# stm32f4.net
KiCad netlist of a schematic drawn in Altium Designer
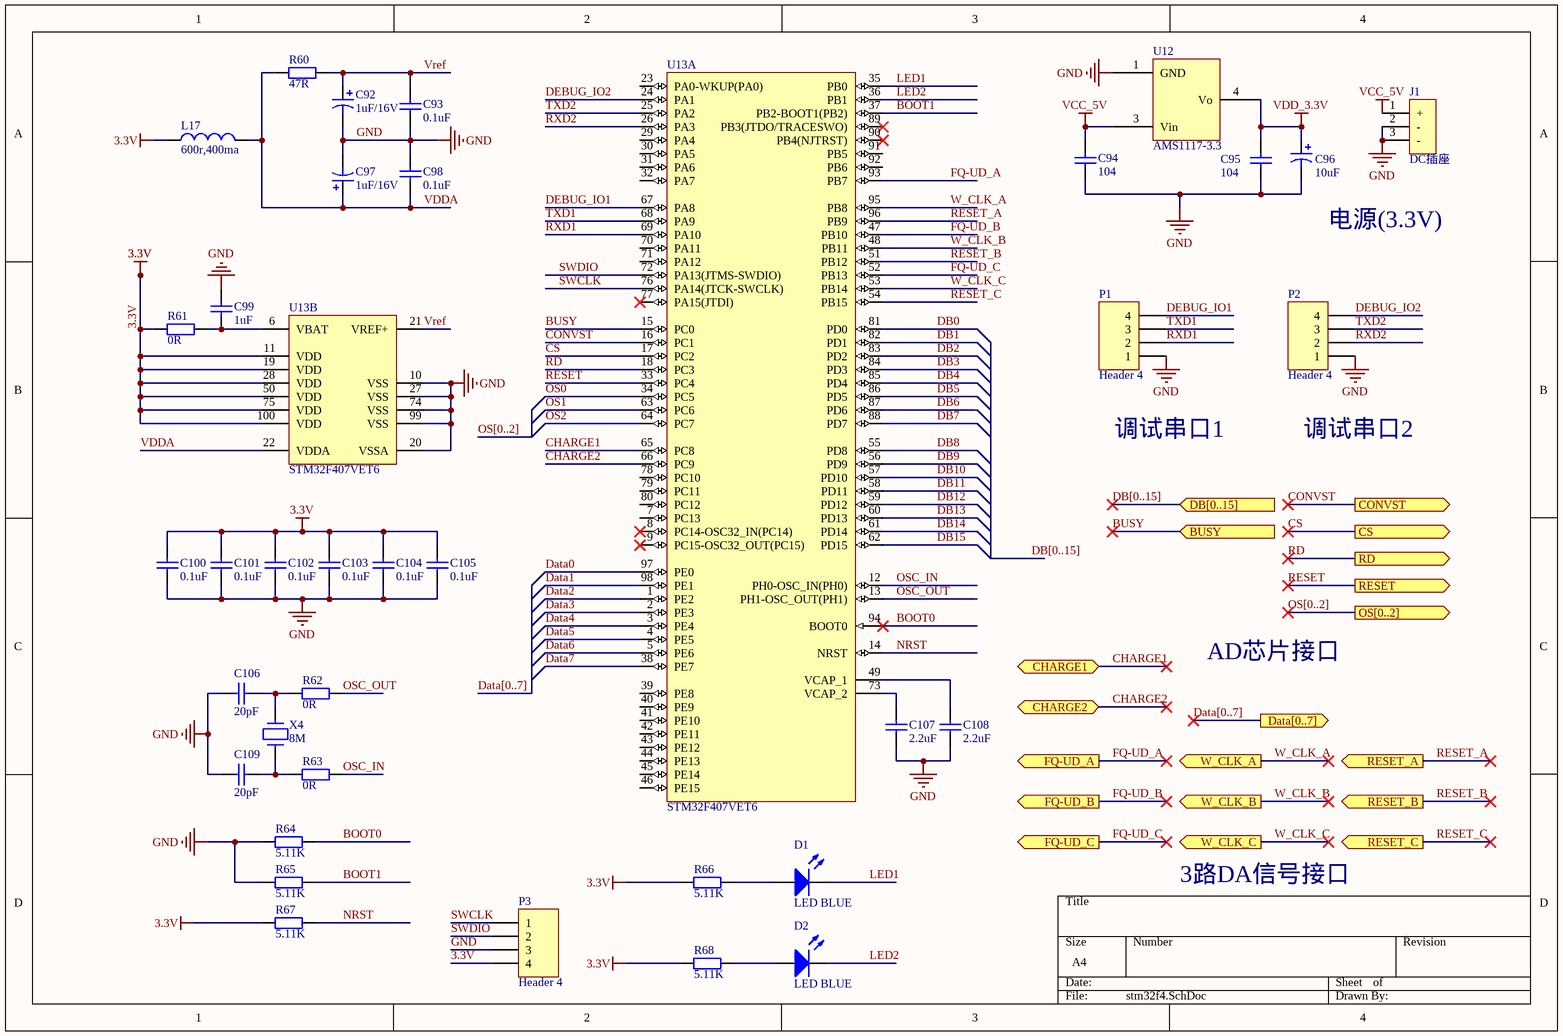
[diagram p0: stm32f4.SchDoc]

(export (version "E")
  (design (tool "Eeschema 10.0.6"))
  (components
    (comp (ref "C92") (value "1uF/16V") (footprint "1206") (libsource (lib "MyLibrary") (part "Cap_Pol")))
    (comp (ref "C93") (value "0.1uF") (footprint "0805C") (libsource (lib "MyLibrary") (part "Cap")))
    (comp (ref "C94")
      (value "104")
      (footprint "0805")
      (fields
        (field (name "Comment") "Cap")
        (field (name "原理图绘制者") "刘永钦")
        (field (name "原理图提供者") "刘永钦")
        (field (name "原理图审核人1") "徐鹏飞")
        (field (name "封装0805绘制者") "刘永钦")
        (field (name "封装0805提供者") "刘永钦")
        (field (name "封装0805审核人1") "徐鹏飞")
        (field (name "原理图审核人2") "朱觉文")
        (field (name "封装0805审核人2") "朱觉文")
        (field (name "封装0603绘制者") "刘永钦")
        (field (name "封装0603提供者") "刘永钦")
        (field (name "封装0603审核人1") "朱觉文")
        (field (name "封装0603审核人2") "徐鹏飞")
      )
      (libsource (lib "自动化研究所集成库20170318") (part "Cap"))
    )
    (comp (ref "C95")
      (value "104")
      (footprint "0805")
      (fields
        (field (name "Comment") "Cap")
        (field (name "原理图绘制者") "刘永钦")
        (field (name "原理图提供者") "刘永钦")
        (field (name "原理图审核人1") "徐鹏飞")
        (field (name "封装0805绘制者") "刘永钦")
        (field (name "封装0805提供者") "刘永钦")
        (field (name "封装0805审核人1") "徐鹏飞")
        (field (name "原理图审核人2") "朱觉文")
        (field (name "封装0805审核人2") "朱觉文")
        (field (name "封装0603绘制者") "刘永钦")
        (field (name "封装0603提供者") "刘永钦")
        (field (name "封装0603审核人1") "朱觉文")
        (field (name "封装0603审核人2") "徐鹏飞")
      )
      (libsource (lib "自动化研究所集成库20170318") (part "Cap"))
    )
    (comp (ref "C96")
      (value "10uF")
      (footprint "Cap 3528B")
      (fields
        (field (name "Comment") "Cap Poll")
        (field (name "原理图绘制者") "刘永钦")
        (field (name "原理图提供者") "刘永钦")
        (field (name "原理图审核人1") "徐鹏飞")
        (field (name "封装CAP 钽 7343 E绘制者") "刘永钦")
        (field (name "封装CAP 钽 7343 E提供者") "刘永钦")
        (field (name "封装CAP 钽 7343 E审核人1") "徐鹏飞")
        (field (name "封装CAP贴片铝电解质470UF 16V绘制者") "李泽")
        (field (name "封装CAP贴片铝电解质470UF 16V提供者") "刘永钦")
        (field (name "封装CAP贴片铝电解质470UF 16V审核人1") "徐鹏飞")
        (field (name "封装CAP 3528B绘制者") "陈汉诚")
        (field (name "封装CAP 3528B提供者") "刘永钦")
        (field (name "封装CAP 3528B审核人1") "徐鹏飞")
        (field (name "封装CAP直插 10UF 50V提供者") "刘永钦")
        (field (name "封装CAP直插 10UF 50V审核人1") "徐鹏飞")
        (field (name "封装CAP 3528B审核人2") "朱觉文")
        (field (name "封装CAP直插 10UF 50V审核人2") "朱觉文")
        (field (name "封装CAP贴片铝电解质470UF 16V审核人2") "朱觉文")
        (field (name "封装CAP 钽 7343 E审核人2") "朱觉文")
        (field (name "原理图审核人2") "朱觉文")
      )
      (libsource (lib "自动化研究所集成库20170318") (part "Cap Poll"))
    )
    (comp (ref "C97") (value "1uF/16V") (footprint "1206") (libsource (lib "MyLibrary") (part "Cap_Pol")))
    (comp (ref "C98") (value "0.1uF") (footprint "0805C") (libsource (lib "MyLibrary") (part "Cap")))
    (comp (ref "C99") (value "1uF") (footprint "0805C") (libsource (lib "MyLibrary") (part "Cap")))
    (comp (ref "C100") (value "0.1uF") (footprint "0805C") (libsource (lib "MyLibrary") (part "Cap")))
    (comp (ref "C101") (value "0.1uF") (footprint "0805C") (libsource (lib "MyLibrary") (part "Cap")))
    (comp (ref "C102") (value "0.1uF") (footprint "0805C") (libsource (lib "MyLibrary") (part "Cap")))
    (comp (ref "C103") (value "0.1uF") (footprint "0805C") (libsource (lib "MyLibrary") (part "Cap")))
    (comp (ref "C104") (value "0.1uF") (footprint "0805C") (libsource (lib "MyLibrary") (part "Cap")))
    (comp (ref "C105") (value "0.1uF") (footprint "0805C") (libsource (lib "MyLibrary") (part "Cap")))
    (comp (ref "C106") (value "20pF") (footprint "0805C") (libsource (lib "MyLibrary") (part "Cap")))
    (comp (ref "C107") (value "2.2uF") (footprint "0805C") (libsource (lib "MyLibrary") (part "Cap")))
    (comp (ref "C108") (value "2.2uF") (footprint "0805C") (libsource (lib "MyLibrary") (part "Cap")))
    (comp (ref "C109") (value "20pF") (footprint "0805C") (libsource (lib "MyLibrary") (part "Cap")))
    (comp (ref "D1") (value "LED BLUE") (footprint "LED_3mm") (libsource (lib "MyLibrary") (part "LED")))
    (comp (ref "D2") (value "LED BLUE") (footprint "LED_3mm") (libsource (lib "MyLibrary") (part "LED")))
    (comp (ref "J1")
      (value "DC插座")
      (footprint "DC插座 5.5mm*2.1mm")
      (fields
        (field (name "原理图审核人2") "朱觉文")
        (field (name "原理图提供者") "刘永钦")
        (field (name "原理图审核人1") "徐鹏飞")
        (field (name "原理图绘制者") "刘永钦")
        (field (name "封装DC插座 5.5MM*2.1MM绘制者") "刘永钦")
        (field (name "封装DC插座 5.5MM*2.1MM提供者") "刘永钦")
        (field (name "封装DC插座 5.5MM*2.1MM审核人1") "徐鹏飞")
        (field (name "封装DC插座 5.5MM*2.1MM审核人2") "朱觉文")
      )
      (libsource (lib "自动化研究所集成库20170318") (part "DC插座"))
    )
    (comp (ref "L17")
      (value "600r,400ma")
      (footprint "0805L")
      (libsource (lib "MyLibrary") (part "Inductor"))
    )
    (comp (ref "P1")
      (value "Header 4")
      (footprint "HDR1X4")
      (description "Header, 4-Pin")
      (fields (field (name "PUBLISHER") "Altium Limited"))
      (libsource (lib "Miscellaneous Connectors") (part "Header 4"))
    )
    (comp (ref "P2")
      (value "Header 4")
      (footprint "HDR1X4")
      (description "Header, 4-Pin")
      (fields (field (name "PUBLISHER") "Altium Limited"))
      (libsource (lib "Miscellaneous Connectors") (part "Header 4"))
    )
    (comp (ref "P3")
      (value "Header 4")
      (footprint "HDR1X4")
      (description "Header, 4-Pin")
      (fields (field (name "PUBLISHER") "Altium Limited"))
      (libsource (lib "") (part "Header 4_1"))
    )
    (comp (ref "R60") (value "47R") (footprint "0805R") (libsource (lib "MyLibrary") (part "Res")))
    (comp (ref "R61") (value "0R") (footprint "0805R") (libsource (lib "MyLibrary") (part "Res")))
    (comp (ref "R62") (value "0R") (footprint "0805R") (libsource (lib "MyLibrary") (part "Res")))
    (comp (ref "R63") (value "0R") (footprint "0805R") (libsource (lib "MyLibrary") (part "Res")))
    (comp (ref "R64") (value "5.11K") (footprint "0805R") (libsource (lib "") (part "Res_1")))
    (comp (ref "R65") (value "5.11K") (footprint "0805R") (libsource (lib "") (part "Res_1")))
    (comp (ref "R66") (value "5.11K") (footprint "0805R") (libsource (lib "") (part "Res_1")))
    (comp (ref "R67") (value "5.11K") (footprint "0805R") (libsource (lib "") (part "Res_1")))
    (comp (ref "R68") (value "5.11K") (footprint "0805R") (libsource (lib "") (part "Res_1")))
    (comp (ref "U12")
      (value "AMS1117-3.3")
      (footprint "TO-252-2L")
      (libsource (lib "Spartan") (part "AMS1117"))
    )
    (comp (ref "U13")
      (value "STM32F407VET6")
      (footprint "pulse_power1:LQFP100")
      (libsource (lib "altium-import") (part "root_0_MC-ARM-STM32F40X_41X-SQ100_"))
    )
    (comp (ref "X4") (value "8M") (footprint "49SMD") (libsource (lib "MyLibrary") (part "Crystal")))
  )
  (nets
    (net (code "1") (name "/BOOT0") (class "Default")
      (node (ref "R64") (pin "1") (pinfunction "1_1") (pintype "passive"))
      (node (ref "U13") (pin "94") (pinfunction "BOOT0_94") (pintype "input"))
    )
    (net (code "2") (name "/BOOT1") (class "Default")
      (node (ref "R65") (pin "1") (pinfunction "1_1") (pintype "passive"))
      (node (ref "U13") (pin "37") (pinfunction "PB2-BOOT1(PB2)_37") (pintype "bidirectional"))
    )
    (net (code "3") (name "/BUSY") (class "Default")
      (node (ref "U13") (pin "15") (pinfunction "PC0_15") (pintype "bidirectional"))
    )
    (net (code "4") (name "/CHARGE1") (class "Default")
      (node (ref "U13") (pin "65") (pinfunction "PC8_65") (pintype "bidirectional"))
    )
    (net (code "5") (name "/CHARGE2") (class "Default")
      (node (ref "U13") (pin "66") (pinfunction "PC9_66") (pintype "bidirectional"))
    )
    (net (code "6") (name "/CONVST") (class "Default")
      (node (ref "U13") (pin "16") (pinfunction "PC1_16") (pintype "bidirectional"))
    )
    (net (code "7") (name "/CS") (class "Default")
      (node (ref "U13") (pin "17") (pinfunction "PC2_17") (pintype "bidirectional"))
    )
    (net (code "8") (name "/DB0") (class "Default")
      (node (ref "U13") (pin "81") (pinfunction "PD0_81") (pintype "bidirectional"))
    )
    (net (code "9") (name "/DB1") (class "Default")
      (node (ref "U13") (pin "82") (pinfunction "PD1_82") (pintype "bidirectional"))
    )
    (net (code "10") (name "/DB2") (class "Default")
      (node (ref "U13") (pin "83") (pinfunction "PD2_83") (pintype "bidirectional"))
    )
    (net (code "11") (name "/DB3") (class "Default")
      (node (ref "U13") (pin "84") (pinfunction "PD3_84") (pintype "bidirectional"))
    )
    (net (code "12") (name "/DB4") (class "Default")
      (node (ref "U13") (pin "85") (pinfunction "PD4_85") (pintype "bidirectional"))
    )
    (net (code "13") (name "/DB5") (class "Default")
      (node (ref "U13") (pin "86") (pinfunction "PD5_86") (pintype "bidirectional"))
    )
    (net (code "14") (name "/DB6") (class "Default")
      (node (ref "U13") (pin "87") (pinfunction "PD6_87") (pintype "bidirectional"))
    )
    (net (code "15") (name "/DB7") (class "Default")
      (node (ref "U13") (pin "88") (pinfunction "PD7_88") (pintype "bidirectional"))
    )
    (net (code "16") (name "/DB8") (class "Default")
      (node (ref "U13") (pin "55") (pinfunction "PD8_55") (pintype "bidirectional"))
    )
    (net (code "17") (name "/DB9") (class "Default")
      (node (ref "U13") (pin "56") (pinfunction "PD9_56") (pintype "bidirectional"))
    )
    (net (code "18") (name "/DB10") (class "Default")
      (node (ref "U13") (pin "57") (pinfunction "PD10_57") (pintype "bidirectional"))
    )
    (net (code "19") (name "/DB11") (class "Default")
      (node (ref "U13") (pin "58") (pinfunction "PD11_58") (pintype "bidirectional"))
    )
    (net (code "20") (name "/DB12") (class "Default")
      (node (ref "U13") (pin "59") (pinfunction "PD12_59") (pintype "bidirectional"))
    )
    (net (code "21") (name "/DB13") (class "Default")
      (node (ref "U13") (pin "60") (pinfunction "PD13_60") (pintype "bidirectional"))
    )
    (net (code "22") (name "/DB14") (class "Default")
      (node (ref "U13") (pin "61") (pinfunction "PD14_61") (pintype "bidirectional"))
    )
    (net (code "23") (name "/DB15") (class "Default")
      (node (ref "U13") (pin "62") (pinfunction "PD15_62") (pintype "bidirectional"))
    )
    (net (code "25") (name "/DEBUG_IO1") (class "Default")
      (node (ref "P1") (pin "4") (pinfunction "4_4") (pintype "passive"))
      (node (ref "U13") (pin "67") (pinfunction "PA8_67") (pintype "bidirectional"))
    )
    (net (code "26") (name "/DEBUG_IO2") (class "Default")
      (node (ref "P2") (pin "4") (pinfunction "4_4") (pintype "passive"))
      (node (ref "U13") (pin "24") (pinfunction "PA1_24") (pintype "bidirectional"))
    )
    (net (code "27") (name "/Data0") (class "Default")
      (node (ref "U13") (pin "97") (pinfunction "PE0_97") (pintype "bidirectional"))
    )
    (net (code "28") (name "/Data1") (class "Default")
      (node (ref "U13") (pin "98") (pinfunction "PE1_98") (pintype "bidirectional"))
    )
    (net (code "29") (name "/Data2") (class "Default")
      (node (ref "U13") (pin "1") (pinfunction "PE2_1") (pintype "bidirectional"))
    )
    (net (code "30") (name "/Data3") (class "Default")
      (node (ref "U13") (pin "2") (pinfunction "PE3_2") (pintype "bidirectional"))
    )
    (net (code "31") (name "/Data4") (class "Default")
      (node (ref "U13") (pin "3") (pinfunction "PE4_3") (pintype "bidirectional"))
    )
    (net (code "32") (name "/Data5") (class "Default")
      (node (ref "U13") (pin "4") (pinfunction "PE5_4") (pintype "bidirectional"))
    )
    (net (code "33") (name "/Data6") (class "Default")
      (node (ref "U13") (pin "5") (pinfunction "PE6_5") (pintype "bidirectional"))
    )
    (net (code "34") (name "/Data7") (class "Default")
      (node (ref "U13") (pin "38") (pinfunction "PE7_38") (pintype "bidirectional"))
    )
    (net (code "36") (name "/FQ-UD_A") (class "Default")
      (node (ref "U13") (pin "93") (pinfunction "PB7_93") (pintype "bidirectional"))
    )
    (net (code "37") (name "/FQ-UD_B") (class "Default")
      (node (ref "U13") (pin "47") (pinfunction "PB10_47") (pintype "bidirectional"))
    )
    (net (code "38") (name "/FQ-UD_C") (class "Default")
      (node (ref "U13") (pin "52") (pinfunction "PB13_52") (pintype "bidirectional"))
    )
    (net (code "39") (name "/LED1") (class "Default")
      (node (ref "D1") (pin "2") (pinfunction "K_2") (pintype "passive"))
      (node (ref "U13") (pin "35") (pinfunction "PB0_35") (pintype "bidirectional"))
    )
    (net (code "40") (name "/LED2") (class "Default")
      (node (ref "D2") (pin "2") (pinfunction "K_2") (pintype "passive"))
      (node (ref "U13") (pin "36") (pinfunction "PB1_36") (pintype "bidirectional"))
    )
    (net (code "41") (name "/NRST") (class "Default")
      (node (ref "R67") (pin "1") (pinfunction "1_1") (pintype "passive"))
      (node (ref "U13") (pin "14") (pinfunction "NRST_14") (pintype "bidirectional"))
    )
    (net (code "42") (name "/OS0") (class "Default")
      (node (ref "U13") (pin "34") (pinfunction "PC5_34") (pintype "bidirectional"))
    )
    (net (code "43") (name "/OS1") (class "Default")
      (node (ref "U13") (pin "63") (pinfunction "PC6_63") (pintype "bidirectional"))
    )
    (net (code "44") (name "/OS2") (class "Default")
      (node (ref "U13") (pin "64") (pinfunction "PC7_64") (pintype "bidirectional"))
    )
    (net (code "45") (name "/OSC_IN") (class "Default")
      (node (ref "R63") (pin "2") (pinfunction "2_2") (pintype "passive"))
      (node (ref "U13") (pin "12") (pinfunction "PH0-OSC_IN(PH0)_12") (pintype "bidirectional"))
    )
    (net (code "46") (name "/OSC_OUT") (class "Default")
      (node (ref "R62") (pin "2") (pinfunction "2_2") (pintype "passive"))
      (node (ref "U13") (pin "13") (pinfunction "PH1-OSC_OUT(PH1)_13") (pintype "bidirectional"))
    )
    (net (code "48") (name "/RD") (class "Default")
      (node (ref "U13") (pin "18") (pinfunction "PC3_18") (pintype "bidirectional"))
    )
    (net (code "49") (name "/RESET") (class "Default")
      (node (ref "U13") (pin "33") (pinfunction "PC4_33") (pintype "bidirectional"))
    )
    (net (code "50") (name "/RESET_A") (class "Default")
      (node (ref "U13") (pin "96") (pinfunction "PB9_96") (pintype "bidirectional"))
    )
    (net (code "51") (name "/RESET_B") (class "Default")
      (node (ref "U13") (pin "51") (pinfunction "PB12_51") (pintype "bidirectional"))
    )
    (net (code "52") (name "/RESET_C") (class "Default")
      (node (ref "U13") (pin "54") (pinfunction "PB15_54") (pintype "bidirectional"))
    )
    (net (code "53") (name "/RXD1") (class "Default")
      (node (ref "P1") (pin "2") (pinfunction "2_2") (pintype "passive"))
      (node (ref "U13") (pin "69") (pinfunction "PA10_69") (pintype "bidirectional"))
    )
    (net (code "54") (name "/RXD2") (class "Default")
      (node (ref "P2") (pin "2") (pinfunction "2_2") (pintype "passive"))
      (node (ref "U13") (pin "26") (pinfunction "PA3_26") (pintype "bidirectional"))
    )
    (net (code "55") (name "/SWCLK") (class "Default")
      (node (ref "P3") (pin "1") (pinfunction "1_1") (pintype "passive"))
      (node (ref "U13") (pin "76") (pinfunction "PA14(JTCK-SWCLK)_76") (pintype "bidirectional"))
    )
    (net (code "56") (name "/SWDIO") (class "Default")
      (node (ref "P3") (pin "2") (pinfunction "2_2") (pintype "passive"))
      (node (ref "U13") (pin "72") (pinfunction "PA13(JTMS-SWDIO)_72") (pintype "bidirectional"))
    )
    (net (code "57") (name "/TXD1") (class "Default")
      (node (ref "P1") (pin "3") (pinfunction "3_3") (pintype "passive"))
      (node (ref "U13") (pin "68") (pinfunction "PA9_68") (pintype "bidirectional"))
    )
    (net (code "58") (name "/TXD2") (class "Default")
      (node (ref "P2") (pin "3") (pinfunction "3_3") (pintype "passive"))
      (node (ref "U13") (pin "25") (pinfunction "PA2_25") (pintype "bidirectional"))
    )
    (net (code "59") (name "/VDDA") (class "Default")
      (node (ref "C97") (pin "1") (pinfunction "1_1") (pintype "passive"))
      (node (ref "C98") (pin "1") (pinfunction "1_1") (pintype "passive"))
      (node (ref "L17") (pin "2") (pinfunction "2_2") (pintype "passive"))
      (node (ref "R60") (pin "1") (pinfunction "1_1") (pintype "passive"))
      (node (ref "U13") (pin "22") (pinfunction "VDDA_22") (pintype "power_in"))
    )
    (net (code "60") (name "/Vref") (class "Default")
      (node (ref "C92") (pin "1") (pinfunction "1_1") (pintype "passive"))
      (node (ref "C93") (pin "2") (pinfunction "2_2") (pintype "passive"))
      (node (ref "R60") (pin "2") (pinfunction "2_2") (pintype "passive"))
      (node (ref "U13") (pin "21") (pinfunction "VREF+_21") (pintype "power_in"))
    )
    (net (code "61") (name "/W_CLK_A") (class "Default")
      (node (ref "U13") (pin "95") (pinfunction "PB8_95") (pintype "bidirectional"))
    )
    (net (code "62") (name "/W_CLK_B") (class "Default")
      (node (ref "U13") (pin "48") (pinfunction "PB11_48") (pintype "bidirectional"))
    )
    (net (code "63") (name "/W_CLK_C") (class "Default")
      (node (ref "U13") (pin "53") (pinfunction "PB14_53") (pintype "bidirectional"))
    )
    (net (code "64") (name "3.3V") (class "Default")
      (node (ref "C100") (pin "2") (pinfunction "2_2") (pintype "passive"))
      (node (ref "C101") (pin "2") (pinfunction "2_2") (pintype "passive"))
      (node (ref "C102") (pin "2") (pinfunction "2_2") (pintype "passive"))
      (node (ref "C103") (pin "2") (pinfunction "2_2") (pintype "passive"))
      (node (ref "C104") (pin "2") (pinfunction "2_2") (pintype "passive"))
      (node (ref "C105") (pin "2") (pinfunction "2_2") (pintype "passive"))
      (node (ref "L17") (pin "1") (pinfunction "1_1") (pintype "passive"))
      (node (ref "P3") (pin "4") (pinfunction "4_4") (pintype "passive"))
      (node (ref "R61") (pin "1") (pinfunction "1_1") (pintype "passive"))
      (node (ref "R66") (pin "2") (pinfunction "2_2") (pintype "passive"))
      (node (ref "R67") (pin "2") (pinfunction "2_2") (pintype "passive"))
      (node (ref "R68") (pin "2") (pinfunction "2_2") (pintype "passive"))
      (node (ref "U13") (pin "100") (pinfunction "VDD_100") (pintype "power_in"))
      (node (ref "U13") (pin "11") (pinfunction "VDD_11") (pintype "power_in"))
      (node (ref "U13") (pin "19") (pinfunction "VDD_19") (pintype "power_in"))
      (node (ref "U13") (pin "28") (pinfunction "VDD_28") (pintype "power_in"))
      (node (ref "U13") (pin "50") (pinfunction "VDD_50") (pintype "power_in"))
      (node (ref "U13") (pin "75") (pinfunction "VDD_75") (pintype "power_in"))
    )
    (net (code "65") (name "GND") (class "Default")
      (node (ref "C100") (pin "1") (pinfunction "1_1") (pintype "passive"))
      (node (ref "C101") (pin "1") (pinfunction "1_1") (pintype "passive"))
      (node (ref "C102") (pin "1") (pinfunction "1_1") (pintype "passive"))
      (node (ref "C103") (pin "1") (pinfunction "1_1") (pintype "passive"))
      (node (ref "C104") (pin "1") (pinfunction "1_1") (pintype "passive"))
      (node (ref "C105") (pin "1") (pinfunction "1_1") (pintype "passive"))
      (node (ref "C106") (pin "1") (pinfunction "1_1") (pintype "passive"))
      (node (ref "C107") (pin "1") (pinfunction "1_1") (pintype "passive"))
      (node (ref "C108") (pin "1") (pinfunction "1_1") (pintype "passive"))
      (node (ref "C109") (pin "1") (pinfunction "1_1") (pintype "passive"))
      (node (ref "C92") (pin "2") (pinfunction "2_2") (pintype "passive"))
      (node (ref "C93") (pin "1") (pinfunction "1_1") (pintype "passive"))
      (node (ref "C94") (pin "1") (pinfunction "1_1") (pintype "passive"))
      (node (ref "C95") (pin "1") (pinfunction "1_1") (pintype "passive"))
      (node (ref "C96") (pin "2") (pinfunction "2_2") (pintype "passive"))
      (node (ref "C97") (pin "2") (pinfunction "2_2") (pintype "passive"))
      (node (ref "C98") (pin "2") (pinfunction "2_2") (pintype "passive"))
      (node (ref "C99") (pin "2") (pinfunction "2_2") (pintype "passive"))
      (node (ref "J1") (pin "2") (pinfunction "-_2") (pintype "power_in"))
      (node (ref "J1") (pin "3") (pinfunction "-_3") (pintype "power_in"))
      (node (ref "P1") (pin "1") (pinfunction "1_1") (pintype "passive"))
      (node (ref "P2") (pin "1") (pinfunction "1_1") (pintype "passive"))
      (node (ref "P3") (pin "3") (pinfunction "3_3") (pintype "passive"))
      (node (ref "R64") (pin "2") (pinfunction "2_2") (pintype "passive"))
      (node (ref "R65") (pin "2") (pinfunction "2_2") (pintype "passive"))
      (node (ref "U12") (pin "1") (pinfunction "GND_1") (pintype "passive"))
      (node (ref "U13") (pin "10") (pinfunction "VSS_10") (pintype "power_in"))
      (node (ref "U13") (pin "20") (pinfunction "VSSA_20") (pintype "power_in"))
      (node (ref "U13") (pin "27") (pinfunction "VSS_27") (pintype "power_in"))
      (node (ref "U13") (pin "74") (pinfunction "VSS_74") (pintype "power_in"))
      (node (ref "U13") (pin "99") (pinfunction "VSS_99") (pintype "power_in"))
    )
    (net (code "66") (name "Net-(C106-Pad2)") (class "Default")
      (node (ref "C106") (pin "2") (pinfunction "2_2") (pintype "passive"))
      (node (ref "R62") (pin "1") (pinfunction "1_1") (pintype "passive"))
      (node (ref "X4") (pin "1") (pinfunction "1_1") (pintype "passive"))
    )
    (net (code "67") (name "Net-(C109-Pad2)") (class "Default")
      (node (ref "C109") (pin "2") (pinfunction "2_2") (pintype "passive"))
      (node (ref "R63") (pin "1") (pinfunction "1_1") (pintype "passive"))
      (node (ref "X4") (pin "2") (pinfunction "2_2") (pintype "passive"))
    )
    (net (code "68") (name "Net-(D1-A)") (class "Default")
      (node (ref "D1") (pin "1") (pinfunction "A_1") (pintype "passive"))
      (node (ref "R66") (pin "1") (pinfunction "1_1") (pintype "passive"))
    )
    (net (code "69") (name "Net-(D2-A)") (class "Default")
      (node (ref "D2") (pin "1") (pinfunction "A_1") (pintype "passive"))
      (node (ref "R68") (pin "1") (pinfunction "1_1") (pintype "passive"))
    )
    (net (code "70") (name "Net-(U13A-VCAP_1)") (class "Default")
      (node (ref "C108") (pin "2") (pinfunction "2_2") (pintype "passive"))
      (node (ref "U13") (pin "49") (pinfunction "VCAP_1_49") (pintype "power_in"))
    )
    (net (code "71") (name "Net-(U13A-VCAP_2)") (class "Default")
      (node (ref "C107") (pin "2") (pinfunction "2_2") (pintype "passive"))
      (node (ref "U13") (pin "73") (pinfunction "VCAP_2_73") (pintype "power_in"))
    )
    (net (code "72") (name "Net-(U13B-VBAT)") (class "Default")
      (node (ref "C99") (pin "1") (pinfunction "1_1") (pintype "passive"))
      (node (ref "R61") (pin "2") (pinfunction "2_2") (pintype "passive"))
      (node (ref "U13") (pin "6") (pinfunction "VBAT_6") (pintype "power_in"))
    )
    (net (code "73") (name "VCC_5V") (class "Default")
      (node (ref "C94") (pin "2") (pinfunction "2_2") (pintype "passive"))
      (node (ref "J1") (pin "1") (pinfunction "+_1") (pintype "power_in"))
      (node (ref "U12") (pin "3") (pinfunction "Vin_3") (pintype "passive"))
    )
    (net (code "74") (name "VDD_3.3V") (class "Default")
      (node (ref "C95") (pin "2") (pinfunction "2_2") (pintype "passive"))
      (node (ref "C96") (pin "1") (pinfunction "1_1") (pintype "passive"))
      (node (ref "U12") (pin "4") (pinfunction "Vo_4") (pintype "passive"))
    )
    (net (code "75") (name "unconnected-(U13A-PA0-WKUP(PA0)-Pad23)") (class "Default")
      (node (ref "U13") (pin "23") (pinfunction "PA0-WKUP(PA0)_23") (pintype "bidirectional"))
    )
    (net (code "76") (name "unconnected-(U13A-PA4-Pad29)") (class "Default")
      (node (ref "U13") (pin "29") (pinfunction "PA4_29") (pintype "bidirectional"))
    )
    (net (code "77") (name "unconnected-(U13A-PA5-Pad30)") (class "Default")
      (node (ref "U13") (pin "30") (pinfunction "PA5_30") (pintype "bidirectional"))
    )
    (net (code "78") (name "unconnected-(U13A-PA6-Pad31)") (class "Default")
      (node (ref "U13") (pin "31") (pinfunction "PA6_31") (pintype "bidirectional"))
    )
    (net (code "79") (name "unconnected-(U13A-PA7-Pad32)") (class "Default")
      (node (ref "U13") (pin "32") (pinfunction "PA7_32") (pintype "bidirectional"))
    )
    (net (code "80") (name "unconnected-(U13A-PA11-Pad70)") (class "Default")
      (node (ref "U13") (pin "70") (pinfunction "PA11_70") (pintype "bidirectional"))
    )
    (net (code "81") (name "unconnected-(U13A-PA12-Pad71)") (class "Default")
      (node (ref "U13") (pin "71") (pinfunction "PA12_71") (pintype "bidirectional"))
    )
    (net (code "82") (name "unconnected-(U13A-PA15(JTDI)-Pad77)") (class "Default")
      (node (ref "U13") (pin "77") (pinfunction "PA15(JTDI)_77") (pintype "bidirectional+no_connect"))
    )
    (net (code "83") (name "unconnected-(U13A-PB3(JTDO{slash}TRACESWO)-Pad89)") (class "Default")
      (node (ref "U13") (pin "89") (pinfunction "PB3(JTDO/TRACESWO)_89") (pintype "bidirectional+no_connect"))
    )
    (net (code "84") (name "unconnected-(U13A-PB4(NJTRST)-Pad90)") (class "Default")
      (node (ref "U13") (pin "90") (pinfunction "PB4(NJTRST)_90") (pintype "bidirectional+no_connect"))
    )
    (net (code "85") (name "unconnected-(U13A-PB5-Pad91)") (class "Default")
      (node (ref "U13") (pin "91") (pinfunction "PB5_91") (pintype "bidirectional"))
    )
    (net (code "86") (name "unconnected-(U13A-PB6-Pad92)") (class "Default")
      (node (ref "U13") (pin "92") (pinfunction "PB6_92") (pintype "bidirectional"))
    )
    (net (code "87") (name "unconnected-(U13A-PC10-Pad78)") (class "Default")
      (node (ref "U13") (pin "78") (pinfunction "PC10_78") (pintype "bidirectional"))
    )
    (net (code "88") (name "unconnected-(U13A-PC11-Pad79)") (class "Default")
      (node (ref "U13") (pin "79") (pinfunction "PC11_79") (pintype "bidirectional"))
    )
    (net (code "89") (name "unconnected-(U13A-PC12-Pad80)") (class "Default")
      (node (ref "U13") (pin "80") (pinfunction "PC12_80") (pintype "bidirectional"))
    )
    (net (code "90") (name "unconnected-(U13A-PC13-Pad7)") (class "Default")
      (node (ref "U13") (pin "7") (pinfunction "PC13_7") (pintype "bidirectional"))
    )
    (net (code "91") (name "unconnected-(U13A-PC14-OSC32_IN(PC14)-Pad8)") (class "Default")
      (node (ref "U13") (pin "8") (pinfunction "PC14-OSC32_IN(PC14)_8") (pintype "bidirectional+no_connect"))
    )
    (net (code "92") (name "unconnected-(U13A-PC15-OSC32_OUT(PC15)-Pad9)") (class "Default")
      (node (ref "U13") (pin "9") (pinfunction "PC15-OSC32_OUT(PC15)_9") (pintype "bidirectional+no_connect"))
    )
    (net (code "93") (name "unconnected-(U13A-PE8-Pad39)") (class "Default")
      (node (ref "U13") (pin "39") (pinfunction "PE8_39") (pintype "bidirectional"))
    )
    (net (code "94") (name "unconnected-(U13A-PE9-Pad40)") (class "Default")
      (node (ref "U13") (pin "40") (pinfunction "PE9_40") (pintype "bidirectional"))
    )
    (net (code "95") (name "unconnected-(U13A-PE10-Pad41)") (class "Default")
      (node (ref "U13") (pin "41") (pinfunction "PE10_41") (pintype "bidirectional"))
    )
    (net (code "96") (name "unconnected-(U13A-PE11-Pad42)") (class "Default")
      (node (ref "U13") (pin "42") (pinfunction "PE11_42") (pintype "bidirectional"))
    )
    (net (code "97") (name "unconnected-(U13A-PE12-Pad43)") (class "Default")
      (node (ref "U13") (pin "43") (pinfunction "PE12_43") (pintype "bidirectional"))
    )
    (net (code "98") (name "unconnected-(U13A-PE13-Pad44)") (class "Default")
      (node (ref "U13") (pin "44") (pinfunction "PE13_44") (pintype "bidirectional"))
    )
    (net (code "99") (name "unconnected-(U13A-PE14-Pad45)") (class "Default")
      (node (ref "U13") (pin "45") (pinfunction "PE14_45") (pintype "bidirectional"))
    )
    (net (code "100") (name "unconnected-(U13A-PE15-Pad46)") (class "Default")
      (node (ref "U13") (pin "46") (pinfunction "PE15_46") (pintype "bidirectional"))
    )
  )
)
